# usb_spi.net
KiCad netlist of a schematic drawn in EAGLE
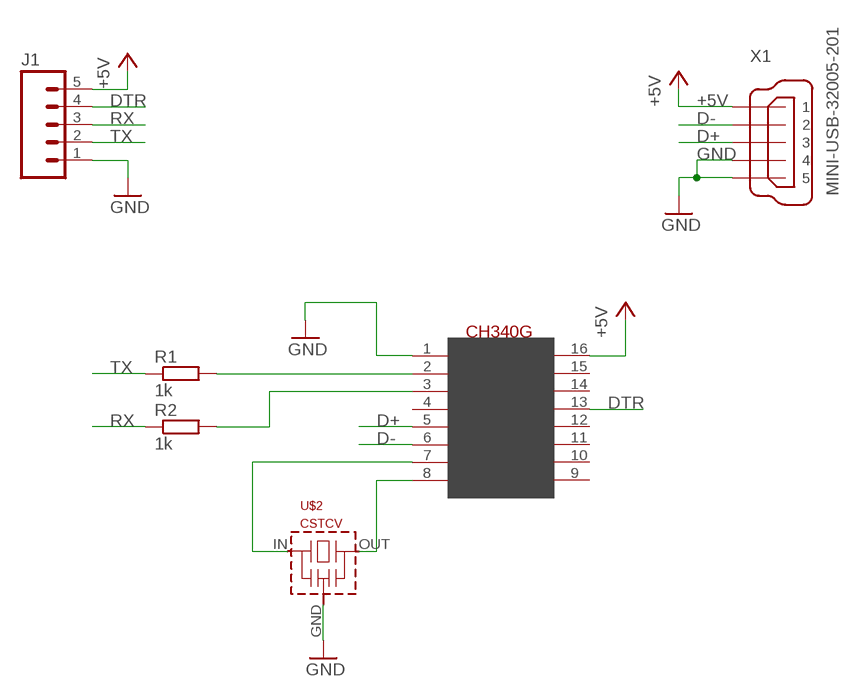
[diagram p0: schematic, sheet 1]

(export (version "E")
  (design (tool "Eeschema 10.0.6"))
  (components
    (comp (ref "J1")
      (value "M05PTH")
      (footprint "eagle-import:1X05")
      (libsource (lib "eagle-import") (part "M05PTH"))
    )
    (comp (ref "R1")
      (value "1k")
      (footprint "eagle-import:R0402")
      (libsource (lib "eagle-import") (part "R-EU_R0402"))
    )
    (comp (ref "R2")
      (value "1k")
      (footprint "eagle-import:R0402")
      (libsource (lib "eagle-import") (part "R-EU_R0402"))
    )
    (comp (ref "U$1")
      (value "CH340G")
      (footprint "eagle-import:SOIC16")
      (libsource (lib "eagle-import") (part "CH340G"))
    )
    (comp (ref "U$2")
      (value "CSTCV")
      (footprint "eagle-import:CSTCV")
      (libsource (lib "eagle-import") (part "CSTCV"))
    )
    (comp (ref "X1")
      (value "MINI-USB-32005-201")
      (footprint "eagle-import:32005-201")
      (libsource (lib "eagle-import") (part "MINI-USB-32005-201"))
    )
  )
  (nets
    (net (code "1") (name "+5V") (class "Default")
      (node (ref "J1") (pin "5") (pinfunction "5_5") (pintype "passive"))
      (node (ref "U$1") (pin "16") (pinfunction "VCC_16") (pintype "bidirectional"))
      (node (ref "X1") (pin "1") (pinfunction "1_1") (pintype "passive"))
    )
    (net (code "2") (name "/D+") (class "Default")
      (node (ref "U$1") (pin "5") (pinfunction "D+_5") (pintype "bidirectional"))
      (node (ref "X1") (pin "3") (pinfunction "3_3") (pintype "passive"))
    )
    (net (code "3") (name "/D-") (class "Default")
      (node (ref "U$1") (pin "6") (pinfunction "D-_6") (pintype "bidirectional"))
      (node (ref "X1") (pin "2") (pinfunction "2_2") (pintype "passive"))
    )
    (net (code "4") (name "/DTR") (class "Default")
      (node (ref "J1") (pin "4") (pinfunction "4_4") (pintype "passive"))
      (node (ref "U$1") (pin "13") (pinfunction "DTR_13") (pintype "bidirectional"))
    )
    (net (code "5") (name "/RX") (class "Default")
      (node (ref "J1") (pin "3") (pinfunction "3_3") (pintype "passive"))
      (node (ref "R2") (pin "1") (pinfunction "1_1") (pintype "passive"))
    )
    (net (code "6") (name "/TX") (class "Default")
      (node (ref "J1") (pin "2") (pinfunction "2_2") (pintype "passive"))
      (node (ref "R1") (pin "1") (pinfunction "1_1") (pintype "passive"))
    )
    (net (code "7") (name "GND") (class "Default")
      (node (ref "J1") (pin "1") (pinfunction "1_1") (pintype "passive"))
      (node (ref "U$1") (pin "1") (pinfunction "GND_1") (pintype "bidirectional"))
      (node (ref "U$2") (pin "GND") (pinfunction "GND_GND") (pintype "power_in"))
      (node (ref "X1") (pin "4") (pinfunction "4_4") (pintype "passive"))
      (node (ref "X1") (pin "5") (pinfunction "5_5") (pintype "passive"))
    )
    (net (code "8") (name "Net-(U$1-RX)") (class "Default")
      (node (ref "R2") (pin "2") (pinfunction "2_2") (pintype "passive"))
      (node (ref "U$1") (pin "3") (pinfunction "RX_3") (pintype "bidirectional"))
    )
    (net (code "9") (name "Net-(U$1-TX)") (class "Default")
      (node (ref "R1") (pin "2") (pinfunction "2_2") (pintype "passive"))
      (node (ref "U$1") (pin "2") (pinfunction "TX_2") (pintype "bidirectional"))
    )
    (net (code "10") (name "Net-(U$1-XI)") (class "Default")
      (node (ref "U$1") (pin "7") (pinfunction "XI_7") (pintype "bidirectional"))
      (node (ref "U$2") (pin "IN") (pinfunction "IN_IN") (pintype "input"))
    )
    (net (code "11") (name "Net-(U$1-XO)") (class "Default")
      (node (ref "U$1") (pin "8") (pinfunction "XO_8") (pintype "bidirectional"))
      (node (ref "U$2") (pin "OUT") (pinfunction "OUT_OUT") (pintype "output"))
    )
    (net (code "12") (name "unconnected-(U$1-CTS-Pad9)") (class "Default")
      (node (ref "U$1") (pin "9") (pinfunction "CTS_9") (pintype "bidirectional"))
    )
    (net (code "13") (name "unconnected-(U$1-DCD-Pad12)") (class "Default")
      (node (ref "U$1") (pin "12") (pinfunction "DCD_12") (pintype "bidirectional"))
    )
    (net (code "14") (name "unconnected-(U$1-DSR-Pad10)") (class "Default")
      (node (ref "U$1") (pin "10") (pinfunction "DSR_10") (pintype "bidirectional"))
    )
    (net (code "15") (name "unconnected-(U$1-RI-Pad11)") (class "Default")
      (node (ref "U$1") (pin "11") (pinfunction "RI_11") (pintype "bidirectional"))
    )
    (net (code "16") (name "unconnected-(U$1-RS232-Pad15)") (class "Default")
      (node (ref "U$1") (pin "15") (pinfunction "RS232_15") (pintype "bidirectional"))
    )
    (net (code "17") (name "unconnected-(U$1-RTS-Pad14)") (class "Default")
      (node (ref "U$1") (pin "14") (pinfunction "RTS_14") (pintype "bidirectional"))
    )
    (net (code "18") (name "unconnected-(U$1-V3-Pad4)") (class "Default")
      (node (ref "U$1") (pin "4") (pinfunction "V3_4") (pintype "bidirectional"))
    )
  )
)
